# gearshift_controller.net
KiCad netlist of a schematic drawn in EAGLE
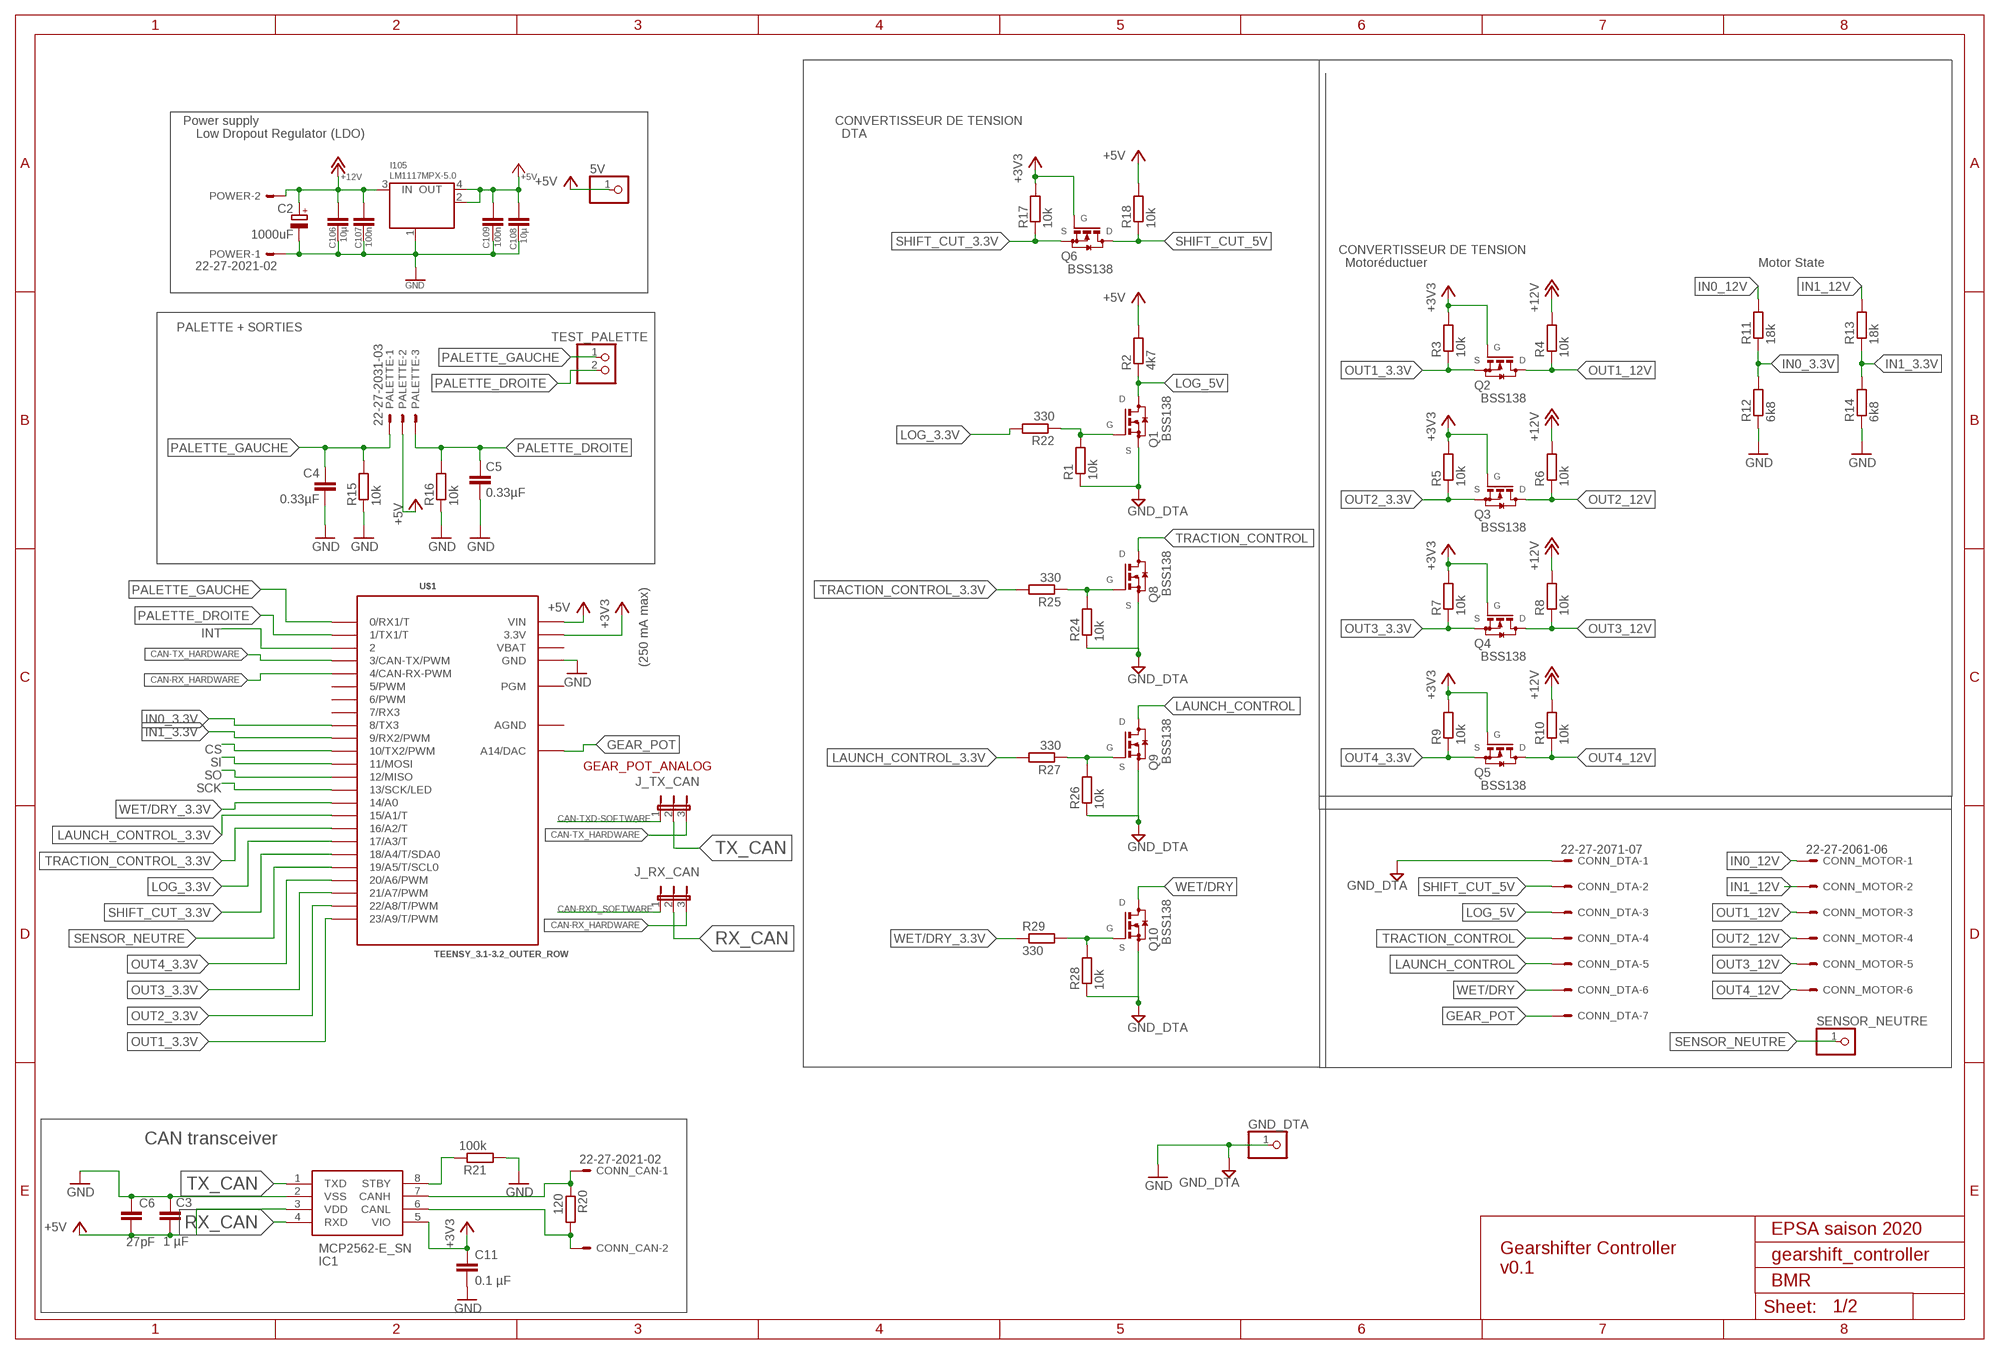
[diagram p0: schematic, sheet 1]
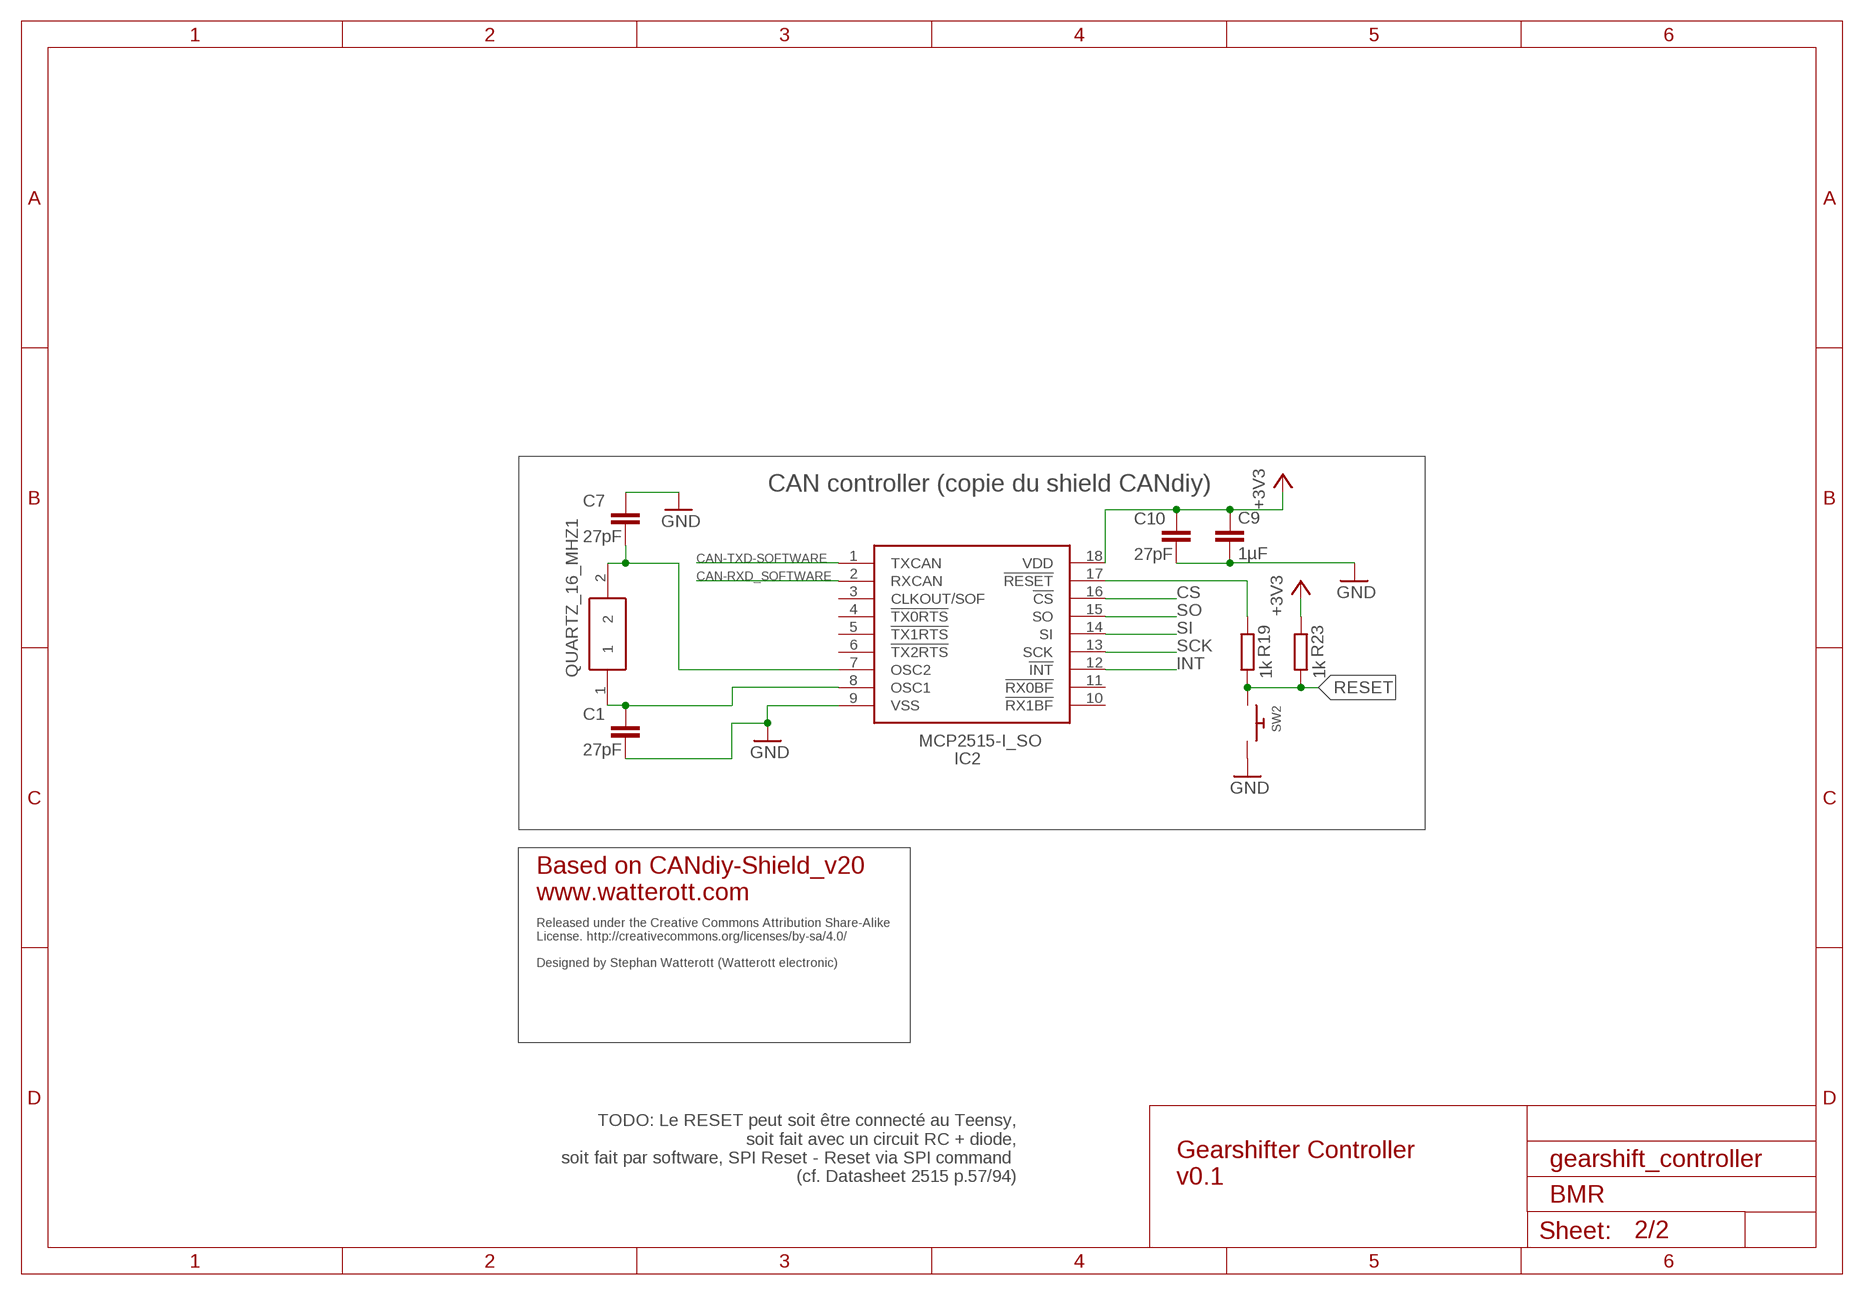
[diagram p1: schematic, sheet 2]

(export (version "E")
  (design (tool "Eeschema 10.0.6"))
  (components
    (comp (ref "5V")
      (value "PINHD-1X1")
      (footprint "eagle-import:1X01")
      (libsource (lib "eagle-import") (part "PINHD-1X1"))
    )
    (comp (ref "C2")
      (value "1000uF")
      (footprint "eagle-import:E25-10")
      (libsource (lib "eagle-import") (part "CPOL-EUE25-10AXIAL"))
    )
    (comp (ref "C3")
      (value "1 µF")
      (footprint "eagle-import:C0805")
      (libsource (lib "eagle-import") (part "rcl_334_C-EUC0805"))
    )
    (comp (ref "C4")
      (value "0.33µF")
      (footprint "eagle-import:C0805")
      (libsource (lib "eagle-import") (part "rcl_334_C-EUC0805"))
    )
    (comp (ref "C5")
      (value "0.33µF")
      (footprint "eagle-import:C0805")
      (libsource (lib "eagle-import") (part "rcl_334_C-EUC0805"))
    )
    (comp (ref "C6")
      (value "27pF")
      (footprint "eagle-import:C0805")
      (libsource (lib "eagle-import") (part "rcl_334_C-EUC0805"))
    )
    (comp (ref "C11")
      (value "0.1 µF")
      (footprint "eagle-import:C0805")
      (libsource (lib "eagle-import") (part "rcl_334_C-EUC0805"))
    )
    (comp (ref "C106")
      (value "10µ")
      (footprint "eagle-import:C0805")
      (libsource (lib "eagle-import") (part "rcl_334_C-EUC0805"))
    )
    (comp (ref "C107")
      (value "100n")
      (footprint "eagle-import:C0603")
      (libsource (lib "eagle-import") (part "C-EUC0603"))
    )
    (comp (ref "C108")
      (value "10µ")
      (footprint "eagle-import:C0805")
      (libsource (lib "eagle-import") (part "rcl_334_C-EUC0805"))
    )
    (comp (ref "C109")
      (value "100n")
      (footprint "eagle-import:C0603")
      (libsource (lib "eagle-import") (part "C-EUC0603"))
    )
    (comp (ref "CONN_CAN")
      (value "22-27-2021-02")
      (footprint "eagle-import:6410-02")
      (fields (field (name "MF") "MOLEX"))
      (libsource (lib "eagle-import") (part "22-?-0227-2021"))
    )
    (comp (ref "CONN_DTA")
      (value "22-27-2071-07")
      (footprint "eagle-import:6410-07")
      (fields (field (name "MF") "MOLEX"))
      (libsource (lib "eagle-import") (part "22-?-0727-2071"))
    )
    (comp (ref "CONN_MOTOR")
      (value "22-27-2061-06")
      (footprint "eagle-import:6410-06")
      (fields (field (name "MF") "MOLEX"))
      (libsource (lib "eagle-import") (part "22-?-0627-2061"))
    )
    (comp (ref "GND_DTA")
      (value "PINHD-1X1")
      (footprint "eagle-import:1X01")
      (libsource (lib "eagle-import") (part "PINHD-1X1"))
    )
    (comp (ref "I105")
      (value "LM1117MPX-5.0")
      (footprint "eagle-import:LINEAR_SOT223")
      (fields (field (name "PART_NUMBER") "LM1117IMPX-5.0"))
      (libsource (lib "eagle-import") (part "0022_LM1117IMPX-5.0"))
    )
    (comp (ref "IC1")
      (value "MCP2562-E_SN")
      (footprint "eagle-import:SOIC127P600X175-8N")
      (fields
        (field (name "MANUFACTURER_PART_NUMBER") "MCP2562-E/SN")
        (field (name "RS_PART_NUMBER") "7990228P")
      )
      (libsource (lib "eagle-import") (part "MCP2562-E_SN"))
    )
    (comp (ref "J_RX_CAN")
      (value "JP2E")
      (footprint "eagle-import:JP2")
      (libsource (lib "eagle-import") (part "JP2E"))
    )
    (comp (ref "J_TX_CAN")
      (value "JP2E")
      (footprint "eagle-import:JP2")
      (libsource (lib "eagle-import") (part "JP2E"))
    )
    (comp (ref "PALETTE")
      (value "22-27-2031-03")
      (footprint "eagle-import:6410-03")
      (fields (field (name "MF") "MOLEX"))
      (libsource (lib "eagle-import") (part "22-?-0327-2031"))
    )
    (comp (ref "POWER")
      (value "22-27-2021-02")
      (footprint "eagle-import:6410-02")
      (fields (field (name "MF") "MOLEX"))
      (libsource (lib "eagle-import") (part "22-?-0227-2021"))
    )
    (comp (ref "Q1")
      (value "BSS138")
      (footprint "eagle-import:SOT23")
      (libsource (lib "eagle-import") (part "BSS123"))
    )
    (comp (ref "Q2")
      (value "BSS138")
      (footprint "eagle-import:SOT23")
      (libsource (lib "eagle-import") (part "BSS123"))
    )
    (comp (ref "Q3")
      (value "BSS138")
      (footprint "eagle-import:SOT23")
      (libsource (lib "eagle-import") (part "BSS123"))
    )
    (comp (ref "Q4")
      (value "BSS138")
      (footprint "eagle-import:SOT23")
      (libsource (lib "eagle-import") (part "BSS123"))
    )
    (comp (ref "Q5")
      (value "BSS138")
      (footprint "eagle-import:SOT23")
      (libsource (lib "eagle-import") (part "BSS123"))
    )
    (comp (ref "Q6")
      (value "BSS138")
      (footprint "eagle-import:SOT23")
      (libsource (lib "eagle-import") (part "BSS123"))
    )
    (comp (ref "Q8")
      (value "BSS138")
      (footprint "eagle-import:SOT23")
      (libsource (lib "eagle-import") (part "BSS123"))
    )
    (comp (ref "Q9")
      (value "BSS138")
      (footprint "eagle-import:SOT23")
      (libsource (lib "eagle-import") (part "BSS123"))
    )
    (comp (ref "Q10")
      (value "BSS138")
      (footprint "eagle-import:SOT23")
      (libsource (lib "eagle-import") (part "BSS123"))
    )
    (comp (ref "R1")
      (value "10k")
      (footprint "eagle-import:R0805")
      (libsource (lib "eagle-import") (part "R-EU_R0805"))
    )
    (comp (ref "R2")
      (value "4k7")
      (footprint "eagle-import:R0805")
      (libsource (lib "eagle-import") (part "R-EU_R0805"))
    )
    (comp (ref "R3")
      (value "10k")
      (footprint "eagle-import:R0805")
      (libsource (lib "eagle-import") (part "R-EU_R0805"))
    )
    (comp (ref "R4")
      (value "10k")
      (footprint "eagle-import:R0805")
      (libsource (lib "eagle-import") (part "R-EU_R0805"))
    )
    (comp (ref "R5")
      (value "10k")
      (footprint "eagle-import:R0805")
      (libsource (lib "eagle-import") (part "R-EU_R0805"))
    )
    (comp (ref "R6")
      (value "10k")
      (footprint "eagle-import:R0805")
      (libsource (lib "eagle-import") (part "R-EU_R0805"))
    )
    (comp (ref "R7")
      (value "10k")
      (footprint "eagle-import:R0805")
      (libsource (lib "eagle-import") (part "R-EU_R0805"))
    )
    (comp (ref "R8")
      (value "10k")
      (footprint "eagle-import:R0805")
      (libsource (lib "eagle-import") (part "R-EU_R0805"))
    )
    (comp (ref "R9")
      (value "10k")
      (footprint "eagle-import:R0805")
      (libsource (lib "eagle-import") (part "R-EU_R0805"))
    )
    (comp (ref "R10")
      (value "10k")
      (footprint "eagle-import:R0805")
      (libsource (lib "eagle-import") (part "R-EU_R0805"))
    )
    (comp (ref "R11")
      (value "18k")
      (footprint "eagle-import:R0805")
      (libsource (lib "eagle-import") (part "R-EU_R0805"))
    )
    (comp (ref "R12")
      (value "6k8")
      (footprint "eagle-import:R0805")
      (libsource (lib "eagle-import") (part "R-EU_R0805"))
    )
    (comp (ref "R13")
      (value "18k")
      (footprint "eagle-import:R0805")
      (libsource (lib "eagle-import") (part "R-EU_R0805"))
    )
    (comp (ref "R14")
      (value "6k8")
      (footprint "eagle-import:R0805")
      (libsource (lib "eagle-import") (part "R-EU_R0805"))
    )
    (comp (ref "R15")
      (value "10k")
      (footprint "eagle-import:R0805")
      (libsource (lib "eagle-import") (part "R-EU_R0805"))
    )
    (comp (ref "R16")
      (value "10k")
      (footprint "eagle-import:R0805")
      (libsource (lib "eagle-import") (part "R-EU_R0805"))
    )
    (comp (ref "R17")
      (value "10k")
      (footprint "eagle-import:R0805")
      (libsource (lib "eagle-import") (part "R-EU_R0805"))
    )
    (comp (ref "R18")
      (value "10k")
      (footprint "eagle-import:R0805")
      (libsource (lib "eagle-import") (part "R-EU_R0805"))
    )
    (comp (ref "R20")
      (value "120")
      (footprint "eagle-import:R0805")
      (libsource (lib "eagle-import") (part "R-EU_R0805"))
    )
    (comp (ref "R21")
      (value "100k")
      (footprint "eagle-import:R0805")
      (libsource (lib "eagle-import") (part "R-EU_R0805"))
    )
    (comp (ref "R22")
      (value "330")
      (footprint "eagle-import:R0805")
      (libsource (lib "eagle-import") (part "R-EU_R0805"))
    )
    (comp (ref "R24")
      (value "10k")
      (footprint "eagle-import:R0805")
      (libsource (lib "eagle-import") (part "R-EU_R0805"))
    )
    (comp (ref "R25")
      (value "330")
      (footprint "eagle-import:R0805")
      (libsource (lib "eagle-import") (part "R-EU_R0805"))
    )
    (comp (ref "R26")
      (value "10k")
      (footprint "eagle-import:R0805")
      (libsource (lib "eagle-import") (part "R-EU_R0805"))
    )
    (comp (ref "R27")
      (value "330")
      (footprint "eagle-import:R0805")
      (libsource (lib "eagle-import") (part "R-EU_R0805"))
    )
    (comp (ref "R28")
      (value "10k")
      (footprint "eagle-import:R0805")
      (libsource (lib "eagle-import") (part "R-EU_R0805"))
    )
    (comp (ref "R29")
      (value "330")
      (footprint "eagle-import:R0805")
      (libsource (lib "eagle-import") (part "R-EU_R0805"))
    )
    (comp (ref "SENSOR_NEUTRE")
      (value "PINHD-1X1")
      (footprint "eagle-import:1X01")
      (libsource (lib "eagle-import") (part "PINHD-1X1"))
    )
    (comp (ref "TEST_PALETTE")
      (value "PINHD-1X2")
      (footprint "eagle-import:1X02")
      (libsource (lib "eagle-import") (part "PINHD-1X2"))
    )
    (comp (ref "U$1")
      (value "TEENSY_3.1-3.2_OUTER_ROW")
      (footprint "eagle-import:TEENSY_3.0-3.2&LC_OUTER_ROW")
      (libsource (lib "eagle-import") (part "TEENSY_3.1-3.2_OUTER_ROW"))
    )
    (comp (ref "C1")
      (value "27pF")
      (footprint "eagle-import:C0805")
      (libsource (lib "eagle-import") (part "rcl_334_C-EUC0805"))
    )
    (comp (ref "C7")
      (value "27pF")
      (footprint "eagle-import:C0805")
      (libsource (lib "eagle-import") (part "rcl_334_C-EUC0805"))
    )
    (comp (ref "C9")
      (value "1µF")
      (footprint "eagle-import:C0805")
      (libsource (lib "eagle-import") (part "rcl_334_C-EUC0805"))
    )
    (comp (ref "C10")
      (value "27pF")
      (footprint "eagle-import:C0805")
      (libsource (lib "eagle-import") (part "rcl_334_C-EUC0805"))
    )
    (comp (ref "IC2")
      (value "MCP2515-I_SO")
      (footprint "eagle-import:SOIC127P1030X265-18N")
      (fields
        (field (name "MANUFACTURER_PART_NUMBER") "MCP2515-I/SO")
        (field (name "RS_PART_NUMBER") "1445765")
      )
      (libsource (lib "eagle-import") (part "MCP2515-I_SO"))
    )
    (comp (ref "QUARTZ_16_MHZ1")
      (value "FOXSLF_160-20")
      (footprint "eagle-import:HC49SLF_1")
      (fields
        (field (name "MANUFACTURER_PART_NUMBER") "FOXSLF/160-20")
        (field (name "RS_PART_NUMBER") "1734298")
      )
      (libsource (lib "eagle-import") (part "FOXSLF_160-20"))
    )
    (comp (ref "R19")
      (value "1k")
      (footprint "eagle-import:R0805")
      (libsource (lib "eagle-import") (part "R-EU_R0805"))
    )
    (comp (ref "R23")
      (value "1k")
      (footprint "eagle-import:R0805")
      (libsource (lib "eagle-import") (part "R-EU_R0805"))
    )
    (comp (ref "SW2")
      (value "SWITCH_PUSHBUTTONEVQ-PE")
      (footprint "eagle-import:TACT_PANA-EVQ")
      (libsource (lib "eagle-import") (part "SWITCH_PUSHBUTTONEVQ-PE"))
    )
  )
  (nets
    (net (code "1") (name "+3V3") (class "Default")
      (node (ref "C10") (pin "1") (pinfunction "1_1") (pintype "passive"))
      (node (ref "C11") (pin "1") (pinfunction "1_1") (pintype "passive"))
      (node (ref "C9") (pin "1") (pinfunction "1_1") (pintype "passive"))
      (node (ref "IC1") (pin "5") (pinfunction "VIO_5") (pintype "bidirectional"))
      (node (ref "IC2") (pin "18") (pinfunction "VDD_18") (pintype "power_in"))
      (node (ref "Q2") (pin "1") (pinfunction "G_1") (pintype "passive"))
      (node (ref "Q3") (pin "1") (pinfunction "G_1") (pintype "passive"))
      (node (ref "Q4") (pin "1") (pinfunction "G_1") (pintype "passive"))
      (node (ref "Q5") (pin "1") (pinfunction "G_1") (pintype "passive"))
      (node (ref "Q6") (pin "1") (pinfunction "G_1") (pintype "passive"))
      (node (ref "R17") (pin "2") (pinfunction "2_2") (pintype "passive"))
      (node (ref "R23") (pin "1") (pinfunction "1_1") (pintype "passive"))
      (node (ref "R3") (pin "2") (pinfunction "2_2") (pintype "passive"))
      (node (ref "R5") (pin "2") (pinfunction "2_2") (pintype "passive"))
      (node (ref "R7") (pin "2") (pinfunction "2_2") (pintype "passive"))
      (node (ref "R9") (pin "2") (pinfunction "2_2") (pintype "passive"))
      (node (ref "U$1") (pin "3.3V") (pinfunction "3.3V_3.3V") (pintype "power_in"))
      (node (ref "U$1") (pin "3.3V1") (pinfunction "3.3V_3.3V1") (pintype "power_in"))
    )
    (net (code "2") (name "+5V") (class "Default")
      (node (ref "5V") (pin "1") (pinfunction "1_1") (pintype "passive"))
      (node (ref "C108") (pin "1") (pinfunction "1_1") (pintype "passive"))
      (node (ref "C109") (pin "2") (pinfunction "2_2") (pintype "passive"))
      (node (ref "C3") (pin "2") (pinfunction "2_2") (pintype "passive"))
      (node (ref "C6") (pin "2") (pinfunction "2_2") (pintype "passive"))
      (node (ref "I105") (pin "2") (pinfunction "OUT_2") (pintype "passive"))
      (node (ref "I105") (pin "4") (pinfunction "OUT_4") (pintype "passive"))
      (node (ref "IC1") (pin "3") (pinfunction "VDD_3") (pintype "bidirectional"))
      (node (ref "PALETTE") (pin "2") (pinfunction "S_2") (pintype "passive"))
      (node (ref "R18") (pin "2") (pinfunction "2_2") (pintype "passive"))
      (node (ref "R2") (pin "2") (pinfunction "2_2") (pintype "passive"))
      (node (ref "U$1") (pin "VIN") (pinfunction "VIN_VIN") (pintype "power_in"))
    )
    (net (code "3") (name "+12V") (class "Default")
      (node (ref "C106") (pin "1") (pinfunction "1_1") (pintype "passive"))
      (node (ref "C107") (pin "1") (pinfunction "1_1") (pintype "passive"))
      (node (ref "C2") (pin "+") (pinfunction "+_+") (pintype "passive"))
      (node (ref "I105") (pin "3") (pinfunction "IN_3") (pintype "input"))
      (node (ref "POWER") (pin "2") (pinfunction "S_2") (pintype "passive"))
      (node (ref "R10") (pin "2") (pinfunction "2_2") (pintype "passive"))
      (node (ref "R4") (pin "2") (pinfunction "2_2") (pintype "passive"))
      (node (ref "R6") (pin "2") (pinfunction "2_2") (pintype "passive"))
      (node (ref "R8") (pin "2") (pinfunction "2_2") (pintype "passive"))
    )
    (net (code "4") (name "AGND") (class "Default")
      (node (ref "U$1") (pin "AGND") (pinfunction "AGND_AGND") (pintype "power_in"))
    )
    (net (code "5") (name "CAN-RXD_SOFTWARE") (class "Default")
      (node (ref "IC2") (pin "2") (pinfunction "RXCAN_2") (pintype "bidirectional"))
      (node (ref "J_RX_CAN") (pin "1") (pinfunction "1_1") (pintype "passive"))
    )
    (net (code "6") (name "CAN-RX_HARDWARE") (class "Default")
      (node (ref "J_RX_CAN") (pin "3") (pinfunction "3_3") (pintype "passive"))
      (node (ref "U$1") (pin "4") (pinfunction "4/CAN-RX-PWM_4") (pintype "bidirectional"))
    )
    (net (code "7") (name "CAN-TXD-SOFTWARE") (class "Default")
      (node (ref "IC2") (pin "1") (pinfunction "TXCAN_1") (pintype "bidirectional"))
      (node (ref "J_TX_CAN") (pin "1") (pinfunction "1_1") (pintype "passive"))
    )
    (net (code "8") (name "CAN-TX_HARDWARE") (class "Default")
      (node (ref "J_TX_CAN") (pin "3") (pinfunction "3_3") (pintype "passive"))
      (node (ref "U$1") (pin "3") (pinfunction "3/CAN-TX/PWM_3") (pintype "bidirectional"))
    )
    (net (code "9") (name "CS") (class "Default")
      (node (ref "IC2") (pin "16") (pinfunction "~{CS}_16") (pintype "input"))
      (node (ref "U$1") (pin "10") (pinfunction "10/TX2/PWM_10") (pintype "bidirectional"))
    )
    (net (code "10") (name "GEAR_POT") (class "Default")
      (node (ref "CONN_DTA") (pin "7") (pinfunction "S_7") (pintype "passive"))
      (node (ref "U$1") (pin "RESET/DAC") (pinfunction "A14/DAC_RESET/DAC") (pintype "bidirectional"))
    )
    (net (code "11") (name "GND") (class "Default")
      (node (ref "C1") (pin "2") (pinfunction "2_2") (pintype "passive"))
      (node (ref "C10") (pin "2") (pinfunction "2_2") (pintype "passive"))
      (node (ref "C106") (pin "2") (pinfunction "2_2") (pintype "passive"))
      (node (ref "C107") (pin "2") (pinfunction "2_2") (pintype "passive"))
      (node (ref "C108") (pin "2") (pinfunction "2_2") (pintype "passive"))
      (node (ref "C109") (pin "1") (pinfunction "1_1") (pintype "passive"))
      (node (ref "C11") (pin "2") (pinfunction "2_2") (pintype "passive"))
      (node (ref "C2") (pin "-") (pinfunction "-_-") (pintype "passive"))
      (node (ref "C3") (pin "1") (pinfunction "1_1") (pintype "passive"))
      (node (ref "C4") (pin "2") (pinfunction "2_2") (pintype "passive"))
      (node (ref "C5") (pin "2") (pinfunction "2_2") (pintype "passive"))
      (node (ref "C6") (pin "1") (pinfunction "1_1") (pintype "passive"))
      (node (ref "C7") (pin "1") (pinfunction "1_1") (pintype "passive"))
      (node (ref "C9") (pin "2") (pinfunction "2_2") (pintype "passive"))
      (node (ref "CONN_DTA") (pin "1") (pinfunction "S_1") (pintype "passive"))
      (node (ref "GND_DTA") (pin "1") (pinfunction "1_1") (pintype "passive"))
      (node (ref "I105") (pin "1") (pinfunction "GND/ADJ_1") (pintype "input"))
      (node (ref "IC1") (pin "2") (pinfunction "VSS_2") (pintype "bidirectional"))
      (node (ref "IC2") (pin "9") (pinfunction "VSS_9") (pintype "power_in"))
      (node (ref "POWER") (pin "1") (pinfunction "S_1") (pintype "passive"))
      (node (ref "Q1") (pin "2") (pinfunction "S_2") (pintype "passive"))
      (node (ref "Q10") (pin "2") (pinfunction "S_2") (pintype "passive"))
      (node (ref "Q8") (pin "2") (pinfunction "S_2") (pintype "passive"))
      (node (ref "Q9") (pin "2") (pinfunction "S_2") (pintype "passive"))
      (node (ref "R1") (pin "1") (pinfunction "1_1") (pintype "passive"))
      (node (ref "R12") (pin "1") (pinfunction "1_1") (pintype "passive"))
      (node (ref "R14") (pin "1") (pinfunction "1_1") (pintype "passive"))
      (node (ref "R15") (pin "1") (pinfunction "1_1") (pintype "passive"))
      (node (ref "R16") (pin "1") (pinfunction "1_1") (pintype "passive"))
      (node (ref "R21") (pin "1") (pinfunction "1_1") (pintype "passive"))
      (node (ref "R24") (pin "1") (pinfunction "1_1") (pintype "passive"))
      (node (ref "R26") (pin "1") (pinfunction "1_1") (pintype "passive"))
      (node (ref "R28") (pin "1") (pinfunction "1_1") (pintype "passive"))
      (node (ref "SW2") (pin "P$2") (pinfunction "P$2_P$2") (pintype "passive"))
      (node (ref "U$1") (pin "GND") (pinfunction "GND_GND") (pintype "power_in"))
      (node (ref "U$1") (pin "GND1") (pinfunction "GND_GND1") (pintype "power_in"))
    )
    (net (code "12") (name "IN0_3.3V") (class "Default")
      (node (ref "R11") (pin "1") (pinfunction "1_1") (pintype "passive"))
      (node (ref "R12") (pin "2") (pinfunction "2_2") (pintype "passive"))
      (node (ref "U$1") (pin "8") (pinfunction "8/TX3_8") (pintype "bidirectional"))
    )
    (net (code "13") (name "IN0_12V") (class "Default")
      (node (ref "CONN_MOTOR") (pin "1") (pinfunction "S_1") (pintype "passive"))
      (node (ref "R11") (pin "2") (pinfunction "2_2") (pintype "passive"))
    )
    (net (code "14") (name "IN1_3.3V") (class "Default")
      (node (ref "R13") (pin "1") (pinfunction "1_1") (pintype "passive"))
      (node (ref "R14") (pin "2") (pinfunction "2_2") (pintype "passive"))
      (node (ref "U$1") (pin "9") (pinfunction "9/RX2/PWM_9") (pintype "bidirectional"))
    )
    (net (code "15") (name "IN1_12V") (class "Default")
      (node (ref "CONN_MOTOR") (pin "2") (pinfunction "S_2") (pintype "passive"))
      (node (ref "R13") (pin "2") (pinfunction "2_2") (pintype "passive"))
    )
    (net (code "16") (name "INT") (class "Default")
      (node (ref "IC2") (pin "12") (pinfunction "~{INT}_12") (pintype "input"))
      (node (ref "U$1") (pin "2") (pinfunction "2_2") (pintype "bidirectional"))
    )
    (net (code "17") (name "LAUNCH_CONTROL") (class "Default")
      (node (ref "CONN_DTA") (pin "5") (pinfunction "S_5") (pintype "passive"))
      (node (ref "Q9") (pin "3") (pinfunction "D_3") (pintype "passive"))
    )
    (net (code "18") (name "LAUNCH_CONTROL_3.3V") (class "Default")
      (node (ref "R27") (pin "2") (pinfunction "2_2") (pintype "passive"))
      (node (ref "U$1") (pin "15/A1") (pinfunction "15/A1/T_15/A1") (pintype "bidirectional"))
    )
    (net (code "19") (name "LOG_3.3V") (class "Default")
      (node (ref "R22") (pin "2") (pinfunction "2_2") (pintype "passive"))
      (node (ref "U$1") (pin "17/A3") (pinfunction "17/A3/T_17/A3") (pintype "bidirectional"))
    )
    (net (code "20") (name "LOG_5V") (class "Default")
      (node (ref "CONN_DTA") (pin "3") (pinfunction "S_3") (pintype "passive"))
      (node (ref "Q1") (pin "3") (pinfunction "D_3") (pintype "passive"))
      (node (ref "R2") (pin "1") (pinfunction "1_1") (pintype "passive"))
    )
    (net (code "21") (name "Net-(CONN_CANA-S)") (class "Default")
      (node (ref "CONN_CAN") (pin "1") (pinfunction "S_1") (pintype "passive"))
      (node (ref "IC1") (pin "7") (pinfunction "CANH_7") (pintype "bidirectional"))
      (node (ref "R20") (pin "1") (pinfunction "1_1") (pintype "passive"))
    )
    (net (code "22") (name "Net-(CONN_CANB-S)") (class "Default")
      (node (ref "CONN_CAN") (pin "2") (pinfunction "S_2") (pintype "passive"))
      (node (ref "IC1") (pin "6") (pinfunction "CANL_6") (pintype "bidirectional"))
      (node (ref "R20") (pin "2") (pinfunction "2_2") (pintype "passive"))
    )
    (net (code "23") (name "Net-(IC1-STBY)") (class "Default")
      (node (ref "IC1") (pin "8") (pinfunction "STBY_8") (pintype "bidirectional"))
      (node (ref "R21") (pin "2") (pinfunction "2_2") (pintype "passive"))
    )
    (net (code "24") (name "Net-(IC2-OSC1)") (class "Default")
      (node (ref "C1") (pin "1") (pinfunction "1_1") (pintype "passive"))
      (node (ref "IC2") (pin "8") (pinfunction "OSC1_8") (pintype "bidirectional"))
      (node (ref "QUARTZ_16_MHZ1") (pin "1") (pinfunction "1_1") (pintype "bidirectional"))
    )
    (net (code "25") (name "Net-(IC2-OSC2)") (class "Default")
      (node (ref "C7") (pin "2") (pinfunction "2_2") (pintype "passive"))
      (node (ref "IC2") (pin "7") (pinfunction "OSC2_7") (pintype "bidirectional"))
      (node (ref "QUARTZ_16_MHZ1") (pin "2") (pinfunction "2_2") (pintype "bidirectional"))
    )
    (net (code "26") (name "Net-(IC2-~{RESET})") (class "Default")
      (node (ref "IC2") (pin "17") (pinfunction "~{RESET}_17") (pintype "bidirectional"))
      (node (ref "R19") (pin "1") (pinfunction "1_1") (pintype "passive"))
    )
    (net (code "27") (name "Net-(Q1-G)") (class "Default")
      (node (ref "Q1") (pin "1") (pinfunction "G_1") (pintype "passive"))
      (node (ref "R1") (pin "2") (pinfunction "2_2") (pintype "passive"))
      (node (ref "R22") (pin "1") (pinfunction "1_1") (pintype "passive"))
    )
    (net (code "28") (name "Net-(Q8-G)") (class "Default")
      (node (ref "Q8") (pin "1") (pinfunction "G_1") (pintype "passive"))
      (node (ref "R24") (pin "2") (pinfunction "2_2") (pintype "passive"))
      (node (ref "R25") (pin "1") (pinfunction "1_1") (pintype "passive"))
    )
    (net (code "29") (name "Net-(Q9-G)") (class "Default")
      (node (ref "Q9") (pin "1") (pinfunction "G_1") (pintype "passive"))
      (node (ref "R26") (pin "2") (pinfunction "2_2") (pintype "passive"))
      (node (ref "R27") (pin "1") (pinfunction "1_1") (pintype "passive"))
    )
    (net (code "30") (name "Net-(Q10-G)") (class "Default")
      (node (ref "Q10") (pin "1") (pinfunction "G_1") (pintype "passive"))
      (node (ref "R28") (pin "2") (pinfunction "2_2") (pintype "passive"))
      (node (ref "R29") (pin "2") (pinfunction "2_2") (pintype "passive"))
    )
    (net (code "31") (name "OUT1_3.3V") (class "Default")
      (node (ref "Q2") (pin "2") (pinfunction "S_2") (pintype "passive"))
      (node (ref "R3") (pin "1") (pinfunction "1_1") (pintype "passive"))
      (node (ref "U$1") (pin "23/A9") (pinfunction "23/A9/T/PWM_23/A9") (pintype "bidirectional"))
    )
    (net (code "32") (name "OUT1_12V") (class "Default")
      (node (ref "CONN_MOTOR") (pin "3") (pinfunction "S_3") (pintype "passive"))
      (node (ref "Q2") (pin "3") (pinfunction "D_3") (pintype "passive"))
      (node (ref "R4") (pin "1") (pinfunction "1_1") (pintype "passive"))
    )
    (net (code "33") (name "OUT2_3.3V") (class "Default")
      (node (ref "Q3") (pin "2") (pinfunction "S_2") (pintype "passive"))
      (node (ref "R5") (pin "1") (pinfunction "1_1") (pintype "passive"))
      (node (ref "U$1") (pin "22/A8") (pinfunction "22/A8/T/PWM_22/A8") (pintype "bidirectional"))
    )
    (net (code "34") (name "OUT2_12V") (class "Default")
      (node (ref "CONN_MOTOR") (pin "4") (pinfunction "S_4") (pintype "passive"))
      (node (ref "Q3") (pin "3") (pinfunction "D_3") (pintype "passive"))
      (node (ref "R6") (pin "1") (pinfunction "1_1") (pintype "passive"))
    )
    (net (code "35") (name "OUT3_3.3V") (class "Default")
      (node (ref "Q4") (pin "2") (pinfunction "S_2") (pintype "passive"))
      (node (ref "R7") (pin "1") (pinfunction "1_1") (pintype "passive"))
      (node (ref "U$1") (pin "21/A7") (pinfunction "21/A7/PWM_21/A7") (pintype "bidirectional"))
    )
    (net (code "36") (name "OUT3_12V") (class "Default")
      (node (ref "CONN_MOTOR") (pin "5") (pinfunction "S_5") (pintype "passive"))
      (node (ref "Q4") (pin "3") (pinfunction "D_3") (pintype "passive"))
      (node (ref "R8") (pin "1") (pinfunction "1_1") (pintype "passive"))
    )
    (net (code "37") (name "OUT4_3.3V") (class "Default")
      (node (ref "Q5") (pin "2") (pinfunction "S_2") (pintype "passive"))
      (node (ref "R9") (pin "1") (pinfunction "1_1") (pintype "passive"))
      (node (ref "U$1") (pin "20/A6") (pinfunction "20/A6/PWM_20/A6") (pintype "bidirectional"))
    )
    (net (code "38") (name "OUT4_12V") (class "Default")
      (node (ref "CONN_MOTOR") (pin "6") (pinfunction "S_6") (pintype "passive"))
      (node (ref "Q5") (pin "3") (pinfunction "D_3") (pintype "passive"))
      (node (ref "R10") (pin "1") (pinfunction "1_1") (pintype "passive"))
    )
    (net (code "39") (name "PALETTE_DROITE") (class "Default")
      (node (ref "C5") (pin "1") (pinfunction "1_1") (pintype "passive"))
      (node (ref "PALETTE") (pin "3") (pinfunction "S_3") (pintype "passive"))
      (node (ref "R16") (pin "2") (pinfunction "2_2") (pintype "passive"))
      (node (ref "TEST_PALETTE") (pin "2") (pinfunction "2_2") (pintype "passive"))
      (node (ref "U$1") (pin "1") (pinfunction "1/TX1/T_1") (pintype "bidirectional"))
    )
    (net (code "40") (name "PALETTE_GAUCHE") (class "Default")
      (node (ref "C4") (pin "1") (pinfunction "1_1") (pintype "passive"))
      (node (ref "PALETTE") (pin "1") (pinfunction "S_1") (pintype "passive"))
      (node (ref "R15") (pin "2") (pinfunction "2_2") (pintype "passive"))
      (node (ref "TEST_PALETTE") (pin "1") (pinfunction "1_1") (pintype "passive"))
      (node (ref "U$1") (pin "0") (pinfunction "0/RX1/T_0") (pintype "bidirectional"))
    )
    (net (code "41") (name "RESET") (class "Default")
      (node (ref "R19") (pin "2") (pinfunction "2_2") (pintype "passive"))
      (node (ref "R23") (pin "2") (pinfunction "2_2") (pintype "passive"))
      (node (ref "SW2") (pin "P$1") (pinfunction "P$1_P$1") (pintype "passive"))
    )
    (net (code "42") (name "RX_CAN") (class "Default")
      (node (ref "IC1") (pin "4") (pinfunction "RXD_4") (pintype "bidirectional"))
      (node (ref "J_RX_CAN") (pin "2") (pinfunction "2_2") (pintype "passive"))
    )
    (net (code "43") (name "SCK") (class "Default")
      (node (ref "IC2") (pin "13") (pinfunction "SCK_13") (pintype "bidirectional"))
      (node (ref "U$1") (pin "13") (pinfunction "13/SCK/LED_13") (pintype "bidirectional"))
    )
    (net (code "44") (name "SENSOR_NEUTRE") (class "Default")
      (node (ref "SENSOR_NEUTRE") (pin "1") (pinfunction "1_1") (pintype "passive"))
      (node (ref "U$1") (pin "19/A5") (pinfunction "19/A5/T/SCL0_19/A5") (pintype "bidirectional"))
    )
    (net (code "45") (name "SHIFT_CUT_3.3V") (class "Default")
      (node (ref "Q6") (pin "2") (pinfunction "S_2") (pintype "passive"))
      (node (ref "R17") (pin "1") (pinfunction "1_1") (pintype "passive"))
      (node (ref "U$1") (pin "18/A4") (pinfunction "18/A4/T/SDA0_18/A4") (pintype "bidirectional"))
    )
    (net (code "46") (name "SHIFT_CUT_5V") (class "Default")
      (node (ref "CONN_DTA") (pin "2") (pinfunction "S_2") (pintype "passive"))
      (node (ref "Q6") (pin "3") (pinfunction "D_3") (pintype "passive"))
      (node (ref "R18") (pin "1") (pinfunction "1_1") (pintype "passive"))
    )
    (net (code "47") (name "SI") (class "Default")
      (node (ref "IC2") (pin "14") (pinfunction "SI_14") (pintype "bidirectional"))
      (node (ref "U$1") (pin "11") (pinfunction "11/MOSI_11") (pintype "bidirectional"))
    )
    (net (code "48") (name "SO") (class "Default")
      (node (ref "IC2") (pin "15") (pinfunction "SO_15") (pintype "bidirectional"))
      (node (ref "U$1") (pin "12") (pinfunction "12/MISO_12") (pintype "bidirectional"))
    )
    (net (code "49") (name "TRACTION_CONTROL") (class "Default")
      (node (ref "CONN_DTA") (pin "4") (pinfunction "S_4") (pintype "passive"))
      (node (ref "Q8") (pin "3") (pinfunction "D_3") (pintype "passive"))
    )
    (net (code "50") (name "TRACTION_CONTROL_3.3V") (class "Default")
      (node (ref "R25") (pin "2") (pinfunction "2_2") (pintype "passive"))
      (node (ref "U$1") (pin "16/A2") (pinfunction "16/A2/T_16/A2") (pintype "bidirectional"))
    )
    (net (code "51") (name "TX_CAN") (class "Default")
      (node (ref "IC1") (pin "1") (pinfunction "TXD_1") (pintype "bidirectional"))
      (node (ref "J_TX_CAN") (pin "2") (pinfunction "2_2") (pintype "passive"))
    )
    (net (code "52") (name "VBAT") (class "Default")
      (node (ref "U$1") (pin "VBAT") (pinfunction "VBAT_VBAT") (pintype "power_in"))
    )
    (net (code "53") (name "WET{slash}DRY") (class "Default")
      (node (ref "CONN_DTA") (pin "6") (pinfunction "S_6") (pintype "passive"))
      (node (ref "Q10") (pin "3") (pinfunction "D_3") (pintype "passive"))
    )
    (net (code "54") (name "WET{slash}DRY_3.3V") (class "Default")
      (node (ref "R29") (pin "1") (pinfunction "1_1") (pintype "passive"))
      (node (ref "U$1") (pin "14/A0") (pinfunction "14/A0_14/A0") (pintype "bidirectional"))
    )
    (net (code "55") (name "unconnected-(IC2-CLKOUT{slash}SOF-Pad3)") (class "Default")
      (node (ref "IC2") (pin "3") (pinfunction "CLKOUT/SOF_3") (pintype "output"))
    )
    (net (code "56") (name "unconnected-(IC2-~{RX0BF}-Pad11)") (class "Default")
      (node (ref "IC2") (pin "11") (pinfunction "~{RX0BF}_11") (pintype "bidirectional"))
    )
    (net (code "57") (name "unconnected-(IC2-~{RX1BF}-Pad10)") (class "Default")
      (node (ref "IC2") (pin "10") (pinfunction "~{RX1BF}_10") (pintype "bidirectional"))
    )
    (net (code "58") (name "unconnected-(IC2-~{TX0RTS}-Pad4)") (class "Default")
      (node (ref "IC2") (pin "4") (pinfunction "~{TX0RTS}_4") (pintype "bidirectional"))
    )
    (net (code "59") (name "unconnected-(IC2-~{TX1RTS}-Pad5)") (class "Default")
      (node (ref "IC2") (pin "5") (pinfunction "~{TX1RTS}_5") (pintype "bidirectional"))
    )
    (net (code "60") (name "unconnected-(IC2-~{TX2RTS}-Pad6)") (class "Default")
      (node (ref "IC2") (pin "6") (pinfunction "~{TX2RTS}_6") (pintype "bidirectional"))
    )
    (net (code "61") (name "unconnected-(U$1-5{slash}PWM-Pad5)") (class "Default")
      (node (ref "U$1") (pin "5") (pinfunction "5/PWM_5") (pintype "bidirectional"))
    )
    (net (code "62") (name "unconnected-(U$1-6{slash}PWM-Pad6)") (class "Default")
      (node (ref "U$1") (pin "6") (pinfunction "6/PWM_6") (pintype "bidirectional"))
    )
    (net (code "63") (name "unconnected-(U$1-7{slash}RX3-Pad7)") (class "Default")
      (node (ref "U$1") (pin "7") (pinfunction "7/RX3_7") (pintype "bidirectional"))
    )
    (net (code "64") (name "unconnected-(U$1-PadPGM)") (class "Default")
      (node (ref "U$1") (pin "PGM") (pinfunction "PGM_PGM") (pintype "bidirectional"))
    )
  )
)
